# cuatudong.net
KiCad netlist of a schematic drawn in Altium Designer
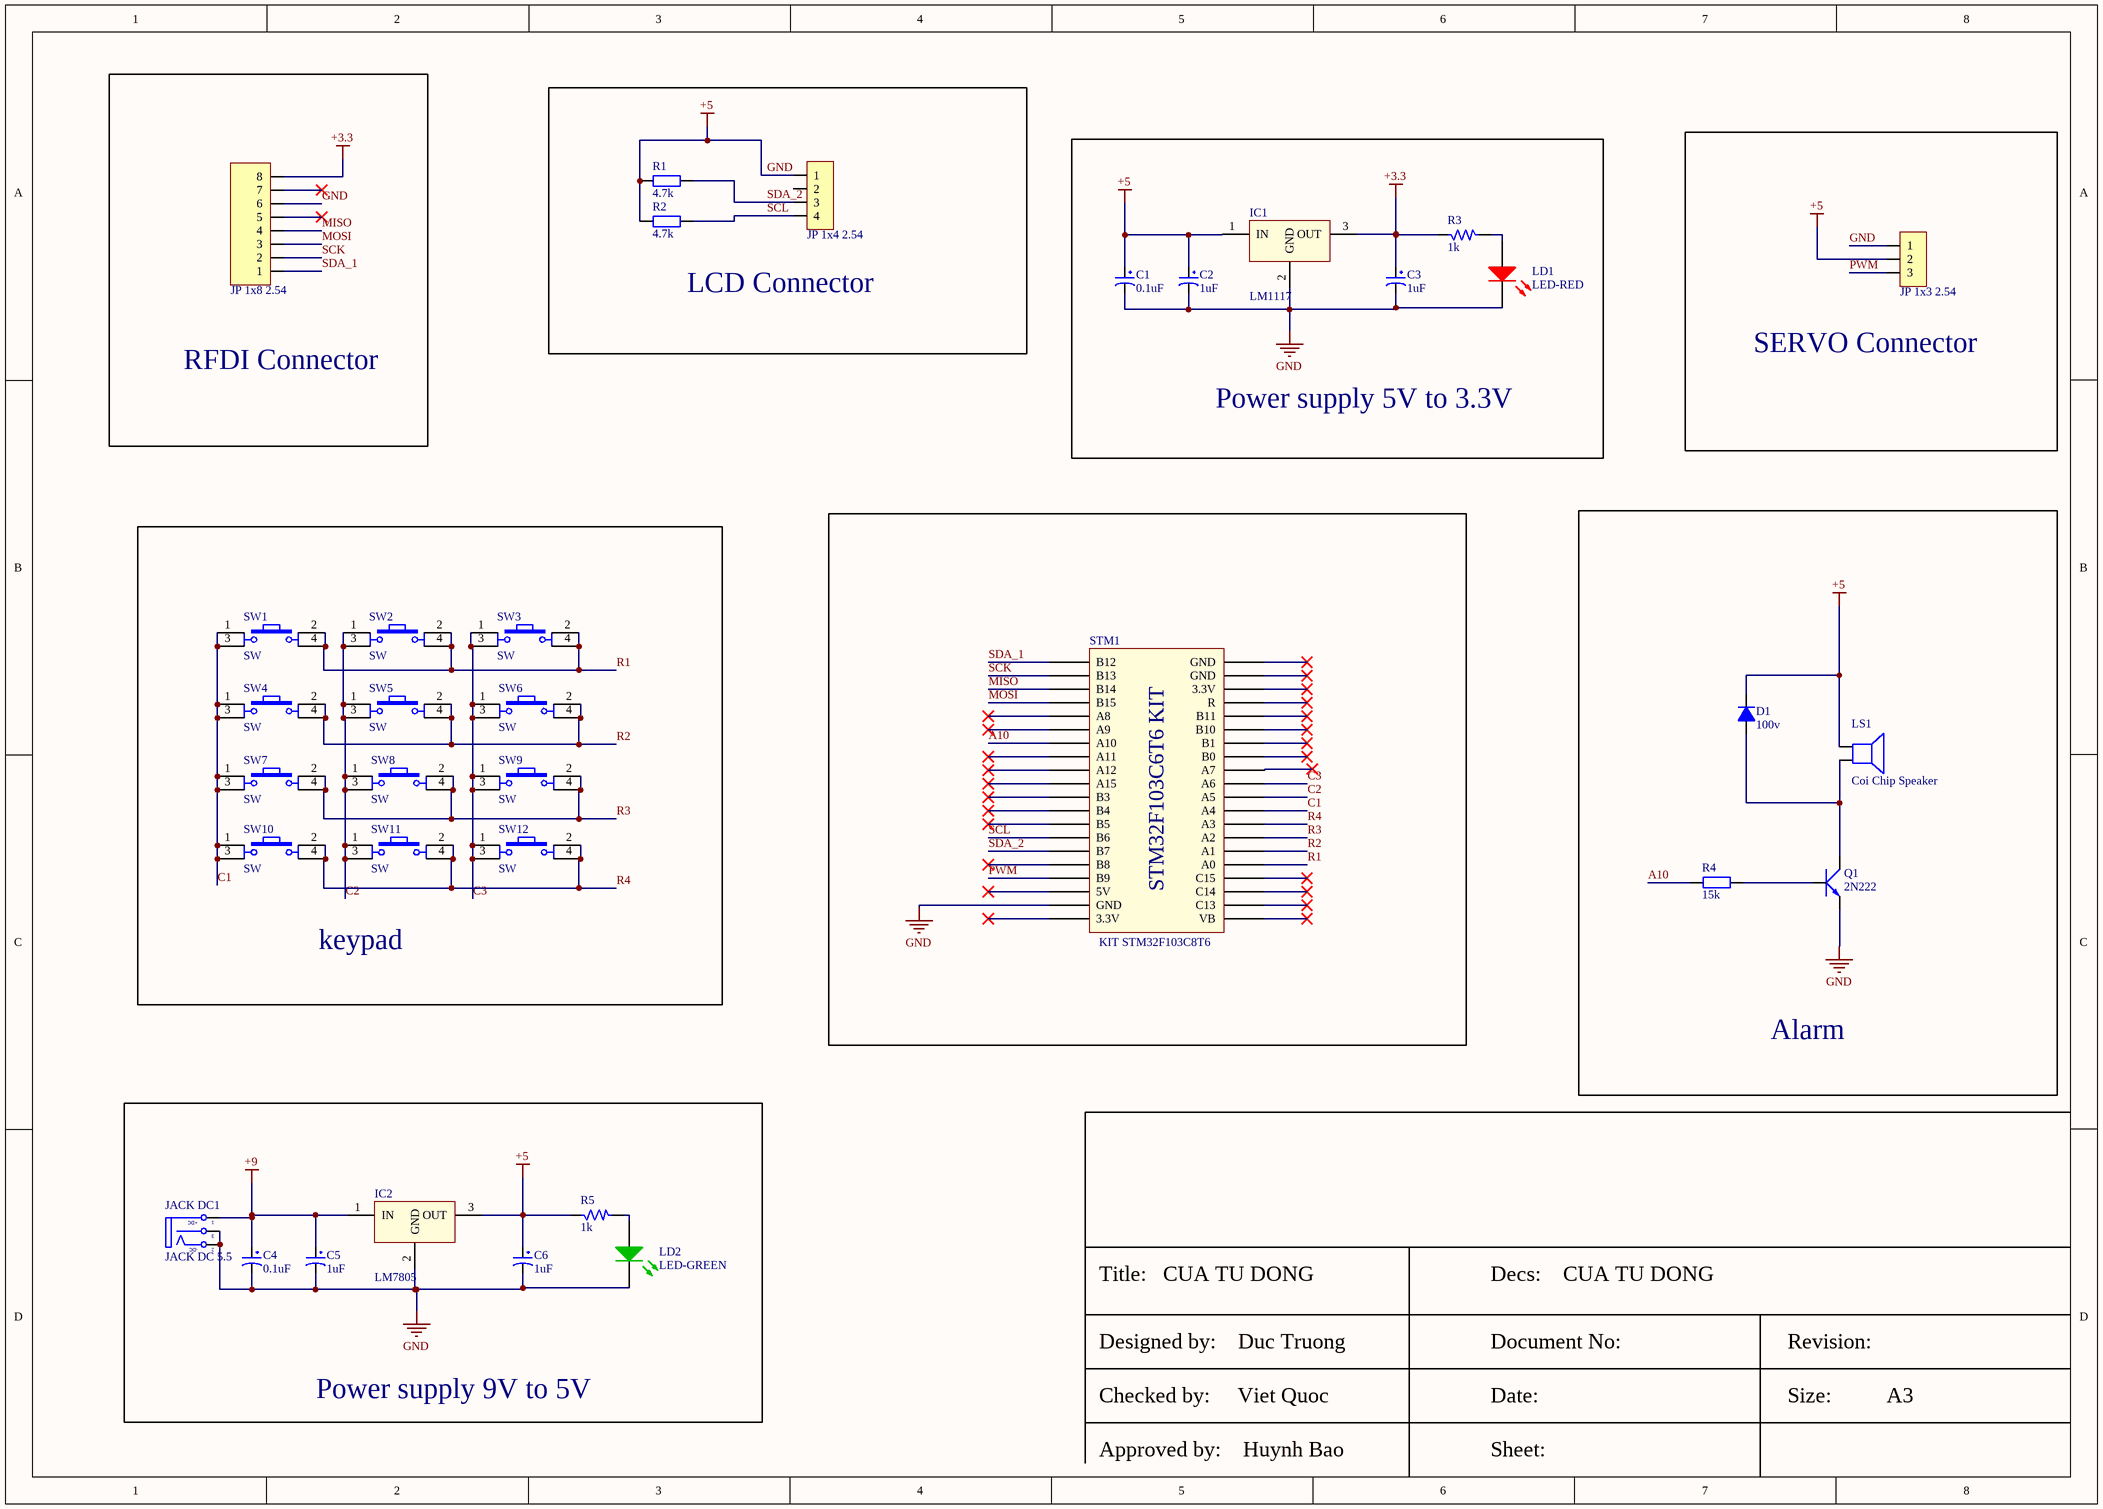
[diagram p0: cuatudong.SchDoc]

(export (version "E")
  (design (tool "Eeschema 10.0.6"))
  (components
    (comp (ref "C1")
      (value "0.1uF")
      (footprint "tu hoa 5mm")
      (description "Cắm")
      (libsource (lib "Altium_Lib_by_KhueNguyenCreator") (part "Tu Hoa 0.1uF 50V 5x11"))
    )
    (comp (ref "C2")
      (value "1uF")
      (footprint "tu hoa 5mm")
      (description "Cắm")
      (libsource (lib "Altium_Lib_by_KhueNguyenCreator") (part "Tu Hoa 1uF 400V 6x10"))
    )
    (comp (ref "C3")
      (value "1uF")
      (footprint "tu hoa 5mm")
      (description "Cắm")
      (libsource (lib "Altium_Lib_by_KhueNguyenCreator") (part "Tu Hoa 1uF 400V 6x10"))
    )
    (comp (ref "C4")
      (value "0.1uF")
      (footprint "tu hoa 5mm")
      (description "Cắm")
      (libsource (lib "Altium_Lib_by_KhueNguyenCreator") (part "Tu Hoa 0.1uF 50V 5x11"))
    )
    (comp (ref "C5")
      (value "1uF")
      (footprint "tu hoa 5mm")
      (description "Cắm")
      (libsource (lib "Altium_Lib_by_KhueNguyenCreator") (part "Tu Hoa 1uF 400V 6x10"))
    )
    (comp (ref "C6")
      (value "1uF")
      (footprint "tu hoa 5mm")
      (description "Cắm")
      (libsource (lib "Altium_Lib_by_KhueNguyenCreator") (part "Tu Hoa 1uF 400V 6x10"))
    )
    (comp (ref "D1")
      (value "100v")
      (footprint "DIODE 0.5A")
      (description "Cắm")
      (libsource (lib "Altium_Lib_by_KhueNguyenCreator") (part "Diode 1N4148"))
    )
    (comp (ref "IC1")
      (value "LM1117")
      (footprint "QTO-220")
      (description "On ap +, from + 5 to + 24VDC")
      (libsource (lib "Devzone_SCHLib") (part "LM78xx"))
    )
    (comp (ref "IC2")
      (value "LM7805")
      (footprint "QTO-220")
      (description "On ap +, from + 5 to + 24VDC")
      (libsource (lib "KhanhBK_SCH_Library_2") (part "LM78xx"))
    )
    (comp (ref "JACK DC1")
      (value "JACK DC 5.5")
      (footprint "JACK DC 5.5")
      (libsource (lib "Altium_Lib_by_KhueNguyenCreator") (part "JACK DC 5.5"))
    )
    (comp (ref "JP1")
      (value "JP 1x8 2.54")
      (footprint "JP 1x8 CT")
      (description "Cắm")
      (libsource (lib "Altium_Lib_by_KhueNguyenCreator") (part "JP 1x8 2.54 Cai Thang"))
    )
    (comp (ref "JP2")
      (value "JP 1x4 2.54")
      (footprint "JP 1x4 CT")
      (description "Cắm")
      (libsource (lib "Altium_Lib_by_KhueNguyenCreator") (part "JP 1x4 2.54 Cai Thang"))
    )
    (comp (ref "JP3")
      (value "JP 1x3 2.54")
      (footprint "JP 1x3 DT")
      (description "Cắm")
      (libsource (lib "Altium_Lib_by_KhueNguyenCreator") (part "JP 1x3 2.54 Duc Thang"))
    )
    (comp (ref "LD1")
      (value "LED-RED")
      (footprint "LED_SMD0603_RED")
      (description "LED RED CLEAR 0603 SMD")
      (fields
        (field (name "MANUFACTURER") "Lite-On Inc.")
        (field (name "MANUFACTURER PART NUMBER") "LTST-C191KRKT")
      )
      (libsource (lib "KhanhBK_SCH_Lib_6") (part "LED_LTST-C191KRKT"))
    )
    (comp (ref "LD2")
      (value "LED-GREEN")
      (footprint "LED_SMD0805_GREEN")
      (description "LED GREEN CLEAR 0805 SMD")
      (fields
        (field (name "MANUFACTURER") "Lite-On Inc.")
        (field (name "MANUFACTURER PART NUMBER") "LTST-C171KGKT")
      )
      (libsource (lib "KhanhBK_SCH_Lib_6") (part "LED_LTST-C171KGKT"))
    )
    (comp (ref "LS1")
      (value "Coi Chip Speaker")
      (footprint "Coi Chip Speacker")
      (description "Còi chip")
      (libsource (lib "Altium_Lib_by_KhueNguyenCreator") (part "Coi Chip Speaker"))
    )
    (comp (ref "Q1")
      (value "2N222")
      (footprint "TO92")
      (description "NPN transistor EBC")
      (libsource (lib "Altium_Lib_by_KhueNguyenCreator") (part "Trans 2N3904"))
    )
    (comp (ref "R1")
      (value "4.7k")
      (footprint "tro cong suat 5w")
      (description "Cắm")
      (libsource (lib "Altium_Lib_by_KhueNguyenCreator") (part "Tro Cong Suat 5W 5% 4.7k"))
    )
    (comp (ref "R2")
      (value "4.7k")
      (footprint "tro cong suat 5w")
      (description "Cắm")
      (libsource (lib "Altium_Lib_by_KhueNguyenCreator") (part "Tro Cong Suat 5W 5% 4.7k"))
    )
    (comp (ref "R3")
      (value "1k")
      (footprint "R1/8W")
      (description "Resistor 1/4W")
      (libsource (lib "Devzone_SCHLib") (part "Res"))
    )
    (comp (ref "R4")
      (value "15k")
      (footprint "tro vach 1/4w")
      (description "Cắm")
      (libsource (lib "Altium_Lib_by_KhueNguyenCreator") (part "Tro Vach 1/4W 5% 15k"))
    )
    (comp (ref "R5")
      (value "1k")
      (footprint "R1/8W")
      (description "Resistor 1/4W")
      (libsource (lib "Devzone_SCHLib") (part "Res"))
    )
    (comp (ref "STM1")
      (value "KIT STM32F103C8T6")
      (footprint "STM32F103 KIT")
      (description "KIT STM32F103C8T6 Bluepill")
      (libsource (lib "Altium_Lib_by_KhueNguyenCreator") (part "STM32f103 Bluepill"))
    )
    (comp (ref "SW1")
      (value "SW")
      (footprint "SW4")
      (description "Switch button 4 pin")
      (libsource (lib "KhanhBK_SCH_Library_2") (part "SW4"))
    )
    (comp (ref "SW2")
      (value "SW")
      (footprint "SW4")
      (description "Switch button 4 pin")
      (libsource (lib "KhanhBK_SCH_Library_2") (part "SW4"))
    )
    (comp (ref "SW3")
      (value "SW")
      (footprint "SW4")
      (description "Switch button 4 pin")
      (libsource (lib "KhanhBK_SCH_Library_2") (part "SW4"))
    )
    (comp (ref "SW4")
      (value "SW")
      (footprint "SW4")
      (description "Switch button 4 pin")
      (libsource (lib "KhanhBK_SCH_Library_2") (part "SW4"))
    )
    (comp (ref "SW5")
      (value "SW")
      (footprint "SW4")
      (description "Switch button 4 pin")
      (libsource (lib "KhanhBK_SCH_Library_2") (part "SW4"))
    )
    (comp (ref "SW6")
      (value "SW")
      (footprint "SW4")
      (description "Switch button 4 pin")
      (libsource (lib "KhanhBK_SCH_Library_2") (part "SW4"))
    )
    (comp (ref "SW7")
      (value "SW")
      (footprint "SW4")
      (description "Switch button 4 pin")
      (libsource (lib "KhanhBK_SCH_Library_2") (part "SW4"))
    )
    (comp (ref "SW8")
      (value "SW")
      (footprint "SW4")
      (description "Switch button 4 pin")
      (libsource (lib "KhanhBK_SCH_Library_2") (part "SW4"))
    )
    (comp (ref "SW9")
      (value "SW")
      (footprint "SW4")
      (description "Switch button 4 pin")
      (libsource (lib "KhanhBK_SCH_Library_2") (part "SW4"))
    )
    (comp (ref "SW10")
      (value "SW")
      (footprint "SW4")
      (description "Switch button 4 pin")
      (libsource (lib "KhanhBK_SCH_Library_2") (part "SW4"))
    )
    (comp (ref "SW11")
      (value "SW")
      (footprint "SW4")
      (description "Switch button 4 pin")
      (libsource (lib "KhanhBK_SCH_Library_2") (part "SW4"))
    )
    (comp (ref "SW12")
      (value "SW")
      (footprint "SW4")
      (description "Switch button 4 pin")
      (libsource (lib "KhanhBK_SCH_Library_2") (part "SW4"))
    )
  )
  (nets
    (net (code "1") (name "+3.3") (class "Default")
      (node (ref "C3") (pin "1") (pinfunction "1_1") (pintype "passive"))
      (node (ref "IC1") (pin "3") (pinfunction "OUT_3") (pintype "passive"))
      (node (ref "JP1") (pin "8") (pinfunction "8_8") (pintype "passive"))
      (node (ref "R3") (pin "1") (pinfunction "1_1") (pintype "passive"))
    )
    (net (code "2") (name "+5") (class "Default")
      (node (ref "C1") (pin "1") (pinfunction "1_1") (pintype "passive"))
      (node (ref "C1") (pin "2") (pinfunction "2_2") (pintype "passive"))
      (node (ref "C2") (pin "1") (pinfunction "1_1") (pintype "passive"))
      (node (ref "C2") (pin "2") (pinfunction "2_2") (pintype "passive"))
      (node (ref "C3") (pin "2") (pinfunction "2_2") (pintype "passive"))
      (node (ref "C4") (pin "2") (pinfunction "2_2") (pintype "passive"))
      (node (ref "C5") (pin "2") (pinfunction "2_2") (pintype "passive"))
      (node (ref "C6") (pin "1") (pinfunction "1_1") (pintype "passive"))
      (node (ref "C6") (pin "2") (pinfunction "2_2") (pintype "passive"))
      (node (ref "D1") (pin "2") (pinfunction "K_2") (pintype "passive"))
      (node (ref "IC1") (pin "1") (pinfunction "IN_1") (pintype "passive"))
      (node (ref "IC1") (pin "2") (pinfunction "GND_2") (pintype "passive"))
      (node (ref "IC2") (pin "2") (pinfunction "GND_2") (pintype "passive"))
      (node (ref "IC2") (pin "3") (pinfunction "OUT_3") (pintype "passive"))
      (node (ref "JACK DC1") (pin "2") (pinfunction "TN_2") (pintype "passive"))
      (node (ref "JACK DC1") (pin "3") (pinfunction "S_3") (pintype "power_in"))
      (node (ref "JP1") (pin "6") (pinfunction "6_6") (pintype "passive"))
      (node (ref "JP2") (pin "1") (pinfunction "1_1") (pintype "passive"))
      (node (ref "JP3") (pin "1") (pinfunction "1_1") (pintype "passive"))
      (node (ref "JP3") (pin "2") (pinfunction "2_2") (pintype "passive"))
      (node (ref "LD1") (pin "2") (pinfunction "K_2") (pintype "passive"))
      (node (ref "LD2") (pin "2") (pinfunction "K_2") (pintype "passive"))
      (node (ref "LS1") (pin "1") (pinfunction "1_1") (pintype "passive"))
      (node (ref "Q1") (pin "1") (pinfunction "E_1") (pintype "passive"))
      (node (ref "R1") (pin "1") (pinfunction "1_1") (pintype "passive"))
      (node (ref "R2") (pin "1") (pinfunction "1_1") (pintype "passive"))
      (node (ref "R5") (pin "1") (pinfunction "1_1") (pintype "passive"))
      (node (ref "STM1") (pin "19") (pinfunction "GND_19") (pintype "passive"))
    )
    (net (code "3") (name "+9") (class "Default")
      (node (ref "C4") (pin "1") (pinfunction "1_1") (pintype "passive"))
      (node (ref "C5") (pin "1") (pinfunction "1_1") (pintype "passive"))
      (node (ref "IC2") (pin "1") (pinfunction "IN_1") (pintype "passive"))
      (node (ref "JACK DC1") (pin "1") (pinfunction "T_1") (pintype "passive"))
    )
    (net (code "4") (name "/A10") (class "Default")
      (node (ref "R4") (pin "1") (pinfunction "1_1") (pintype "passive"))
      (node (ref "STM1") (pin "7") (pinfunction "A10_7") (pintype "passive"))
    )
    (net (code "5") (name "/C1") (class "Default")
      (node (ref "STM1") (pin "29") (pinfunction "A4_29") (pintype "passive"))
      (node (ref "SW1") (pin "1") (pintype "passive"))
      (node (ref "SW1") (pin "3") (pintype "passive"))
      (node (ref "SW10") (pin "1") (pintype "passive"))
      (node (ref "SW10") (pin "3") (pintype "passive"))
      (node (ref "SW4") (pin "1") (pintype "passive"))
      (node (ref "SW4") (pin "3") (pintype "passive"))
      (node (ref "SW7") (pin "1") (pintype "passive"))
      (node (ref "SW7") (pin "3") (pintype "passive"))
    )
    (net (code "6") (name "/C2") (class "Default")
      (node (ref "STM1") (pin "30") (pinfunction "A5_30") (pintype "passive"))
      (node (ref "SW11") (pin "1") (pintype "passive"))
      (node (ref "SW11") (pin "3") (pintype "passive"))
      (node (ref "SW2") (pin "1") (pintype "passive"))
      (node (ref "SW2") (pin "3") (pintype "passive"))
      (node (ref "SW5") (pin "1") (pintype "passive"))
      (node (ref "SW5") (pin "3") (pintype "passive"))
      (node (ref "SW8") (pin "1") (pintype "passive"))
      (node (ref "SW8") (pin "3") (pintype "passive"))
    )
    (net (code "7") (name "/C3") (class "Default")
      (node (ref "STM1") (pin "31") (pinfunction "A6_31") (pintype "passive"))
      (node (ref "SW12") (pin "1") (pintype "passive"))
      (node (ref "SW12") (pin "3") (pintype "passive"))
      (node (ref "SW3") (pin "1") (pintype "passive"))
      (node (ref "SW3") (pin "3") (pintype "passive"))
      (node (ref "SW6") (pin "1") (pintype "passive"))
      (node (ref "SW6") (pin "3") (pintype "passive"))
      (node (ref "SW9") (pin "1") (pintype "passive"))
      (node (ref "SW9") (pin "3") (pintype "passive"))
    )
    (net (code "8") (name "/MISO") (class "Default")
      (node (ref "JP1") (pin "4") (pinfunction "4_4") (pintype "passive"))
      (node (ref "STM1") (pin "3") (pinfunction "B14_3") (pintype "passive"))
    )
    (net (code "9") (name "/MOSI") (class "Default")
      (node (ref "JP1") (pin "3") (pinfunction "3_3") (pintype "passive"))
      (node (ref "STM1") (pin "4") (pinfunction "B15_4") (pintype "passive"))
    )
    (net (code "10") (name "/PWM") (class "Default")
      (node (ref "JP3") (pin "3") (pinfunction "3_3") (pintype "passive"))
      (node (ref "STM1") (pin "17") (pinfunction "B9_17") (pintype "passive"))
    )
    (net (code "11") (name "/R1") (class "Default")
      (node (ref "STM1") (pin "25") (pinfunction "A0_25") (pintype "passive"))
      (node (ref "SW1") (pin "2") (pintype "passive"))
      (node (ref "SW1") (pin "4") (pintype "passive"))
      (node (ref "SW2") (pin "2") (pintype "passive"))
      (node (ref "SW2") (pin "4") (pintype "passive"))
      (node (ref "SW3") (pin "2") (pintype "passive"))
      (node (ref "SW3") (pin "4") (pintype "passive"))
    )
    (net (code "12") (name "/R2") (class "Default")
      (node (ref "STM1") (pin "26") (pinfunction "A1_26") (pintype "passive"))
      (node (ref "SW4") (pin "2") (pintype "passive"))
      (node (ref "SW4") (pin "4") (pintype "passive"))
      (node (ref "SW5") (pin "2") (pintype "passive"))
      (node (ref "SW5") (pin "4") (pintype "passive"))
      (node (ref "SW6") (pin "2") (pintype "passive"))
      (node (ref "SW6") (pin "4") (pintype "passive"))
    )
    (net (code "13") (name "/R3") (class "Default")
      (node (ref "STM1") (pin "27") (pinfunction "A2_27") (pintype "passive"))
      (node (ref "SW7") (pin "2") (pintype "passive"))
      (node (ref "SW7") (pin "4") (pintype "passive"))
      (node (ref "SW8") (pin "2") (pintype "passive"))
      (node (ref "SW8") (pin "4") (pintype "passive"))
      (node (ref "SW9") (pin "2") (pintype "passive"))
      (node (ref "SW9") (pin "4") (pintype "passive"))
    )
    (net (code "14") (name "/R4") (class "Default")
      (node (ref "STM1") (pin "28") (pinfunction "A3_28") (pintype "passive"))
      (node (ref "SW10") (pin "2") (pintype "passive"))
      (node (ref "SW10") (pin "4") (pintype "passive"))
      (node (ref "SW11") (pin "2") (pintype "passive"))
      (node (ref "SW11") (pin "4") (pintype "passive"))
      (node (ref "SW12") (pin "2") (pintype "passive"))
      (node (ref "SW12") (pin "4") (pintype "passive"))
    )
    (net (code "15") (name "/SCK") (class "Default")
      (node (ref "JP1") (pin "2") (pinfunction "2_2") (pintype "passive"))
      (node (ref "STM1") (pin "2") (pinfunction "B13_2") (pintype "passive"))
    )
    (net (code "16") (name "/SCL") (class "Default")
      (node (ref "JP2") (pin "4") (pinfunction "4_4") (pintype "passive"))
      (node (ref "R2") (pin "2") (pinfunction "2_2") (pintype "passive"))
      (node (ref "STM1") (pin "14") (pinfunction "B6_14") (pintype "passive"))
    )
    (net (code "17") (name "/SDA_1") (class "Default")
      (node (ref "JP1") (pin "1") (pinfunction "1_1") (pintype "passive"))
      (node (ref "STM1") (pin "1") (pinfunction "B12_1") (pintype "passive"))
    )
    (net (code "18") (name "/SDA_2") (class "Default")
      (node (ref "JP2") (pin "3") (pinfunction "3_3") (pintype "passive"))
      (node (ref "R1") (pin "2") (pinfunction "2_2") (pintype "passive"))
      (node (ref "STM1") (pin "15") (pinfunction "B7_15") (pintype "passive"))
    )
    (net (code "19") (name "Net-(D1-A)") (class "Default")
      (node (ref "D1") (pin "1") (pinfunction "A_1") (pintype "passive"))
      (node (ref "LS1") (pin "2") (pinfunction "2_2") (pintype "passive"))
      (node (ref "Q1") (pin "3") (pinfunction "C_3") (pintype "passive"))
    )
    (net (code "20") (name "Net-(LD1-A)") (class "Default")
      (node (ref "LD1") (pin "1") (pinfunction "A_1") (pintype "passive"))
      (node (ref "R3") (pin "2") (pinfunction "2_2") (pintype "passive"))
    )
    (net (code "21") (name "Net-(LD2-A)") (class "Default")
      (node (ref "LD2") (pin "1") (pinfunction "A_1") (pintype "passive"))
      (node (ref "R5") (pin "2") (pinfunction "2_2") (pintype "passive"))
    )
    (net (code "22") (name "Net-(Q1-B)") (class "Default")
      (node (ref "Q1") (pin "2") (pinfunction "B_2") (pintype "passive"))
      (node (ref "R4") (pin "2") (pinfunction "2_2") (pintype "passive"))
    )
    (net (code "23") (name "unconnected-(JP1-Pad5)") (class "Default")
      (node (ref "JP1") (pin "5") (pinfunction "5_5") (pintype "passive+no_connect"))
    )
    (net (code "24") (name "unconnected-(JP1-Pad7)") (class "Default")
      (node (ref "JP1") (pin "7") (pinfunction "7_7") (pintype "passive+no_connect"))
    )
    (net (code "25") (name "unconnected-(JP2-Pad2)") (class "Default")
      (node (ref "JP2") (pin "2") (pinfunction "2_2") (pintype "passive"))
    )
    (net (code "26") (name "unconnected-(STM1-3.3V-Pad20)") (class "Default")
      (node (ref "STM1") (pin "20") (pinfunction "3.3V_20") (pintype "passive+no_connect"))
    )
    (net (code "27") (name "unconnected-(STM1-3.3V-Pad38)") (class "Default")
      (node (ref "STM1") (pin "38") (pinfunction "3.3V_38") (pintype "passive+no_connect"))
    )
    (net (code "28") (name "unconnected-(STM1-5V-Pad18)") (class "Default")
      (node (ref "STM1") (pin "18") (pinfunction "5V_18") (pintype "passive+no_connect"))
    )
    (net (code "29") (name "unconnected-(STM1-A7-Pad32)") (class "Default")
      (node (ref "STM1") (pin "32") (pinfunction "A7_32") (pintype "passive+no_connect"))
    )
    (net (code "30") (name "unconnected-(STM1-A8-Pad5)") (class "Default")
      (node (ref "STM1") (pin "5") (pinfunction "A8_5") (pintype "passive+no_connect"))
    )
    (net (code "31") (name "unconnected-(STM1-A9-Pad6)") (class "Default")
      (node (ref "STM1") (pin "6") (pinfunction "A9_6") (pintype "passive+no_connect"))
    )
    (net (code "32") (name "unconnected-(STM1-A11-Pad8)") (class "Default")
      (node (ref "STM1") (pin "8") (pinfunction "A11_8") (pintype "passive+no_connect"))
    )
    (net (code "33") (name "unconnected-(STM1-A12-Pad9)") (class "Default")
      (node (ref "STM1") (pin "9") (pinfunction "A12_9") (pintype "passive+no_connect"))
    )
    (net (code "34") (name "unconnected-(STM1-A15-Pad10)") (class "Default")
      (node (ref "STM1") (pin "10") (pinfunction "A15_10") (pintype "passive+no_connect"))
    )
    (net (code "35") (name "unconnected-(STM1-B0-Pad33)") (class "Default")
      (node (ref "STM1") (pin "33") (pinfunction "B0_33") (pintype "passive+no_connect"))
    )
    (net (code "36") (name "unconnected-(STM1-B1-Pad34)") (class "Default")
      (node (ref "STM1") (pin "34") (pinfunction "B1_34") (pintype "passive+no_connect"))
    )
    (net (code "37") (name "unconnected-(STM1-B3-Pad11)") (class "Default")
      (node (ref "STM1") (pin "11") (pinfunction "B3_11") (pintype "passive+no_connect"))
    )
    (net (code "38") (name "unconnected-(STM1-B4-Pad12)") (class "Default")
      (node (ref "STM1") (pin "12") (pinfunction "B4_12") (pintype "passive+no_connect"))
    )
    (net (code "39") (name "unconnected-(STM1-B5-Pad13)") (class "Default")
      (node (ref "STM1") (pin "13") (pinfunction "B5_13") (pintype "passive+no_connect"))
    )
    (net (code "40") (name "unconnected-(STM1-B8-Pad16)") (class "Default")
      (node (ref "STM1") (pin "16") (pinfunction "B8_16") (pintype "passive+no_connect"))
    )
    (net (code "41") (name "unconnected-(STM1-B10-Pad35)") (class "Default")
      (node (ref "STM1") (pin "35") (pinfunction "B10_35") (pintype "passive+no_connect"))
    )
    (net (code "42") (name "unconnected-(STM1-B11-Pad36)") (class "Default")
      (node (ref "STM1") (pin "36") (pinfunction "B11_36") (pintype "passive+no_connect"))
    )
    (net (code "43") (name "unconnected-(STM1-C13-Pad22)") (class "Default")
      (node (ref "STM1") (pin "22") (pinfunction "C13_22") (pintype "passive+no_connect"))
    )
    (net (code "44") (name "unconnected-(STM1-C14-Pad23)") (class "Default")
      (node (ref "STM1") (pin "23") (pinfunction "C14_23") (pintype "passive+no_connect"))
    )
    (net (code "45") (name "unconnected-(STM1-C15-Pad24)") (class "Default")
      (node (ref "STM1") (pin "24") (pinfunction "C15_24") (pintype "passive+no_connect"))
    )
    (net (code "46") (name "unconnected-(STM1-GND-Pad39)") (class "Default")
      (node (ref "STM1") (pin "39") (pinfunction "GND_39") (pintype "passive+no_connect"))
    )
    (net (code "47") (name "unconnected-(STM1-GND-Pad40)") (class "Default")
      (node (ref "STM1") (pin "40") (pinfunction "GND_40") (pintype "passive+no_connect"))
    )
    (net (code "48") (name "unconnected-(STM1-R-Pad37)") (class "Default")
      (node (ref "STM1") (pin "37") (pinfunction "R_37") (pintype "passive+no_connect"))
    )
    (net (code "49") (name "unconnected-(STM1-VB-Pad21)") (class "Default")
      (node (ref "STM1") (pin "21") (pinfunction "VB_21") (pintype "passive+no_connect"))
    )
  )
)
